# punta.net
KiCad netlist of a schematic drawn in EAGLE
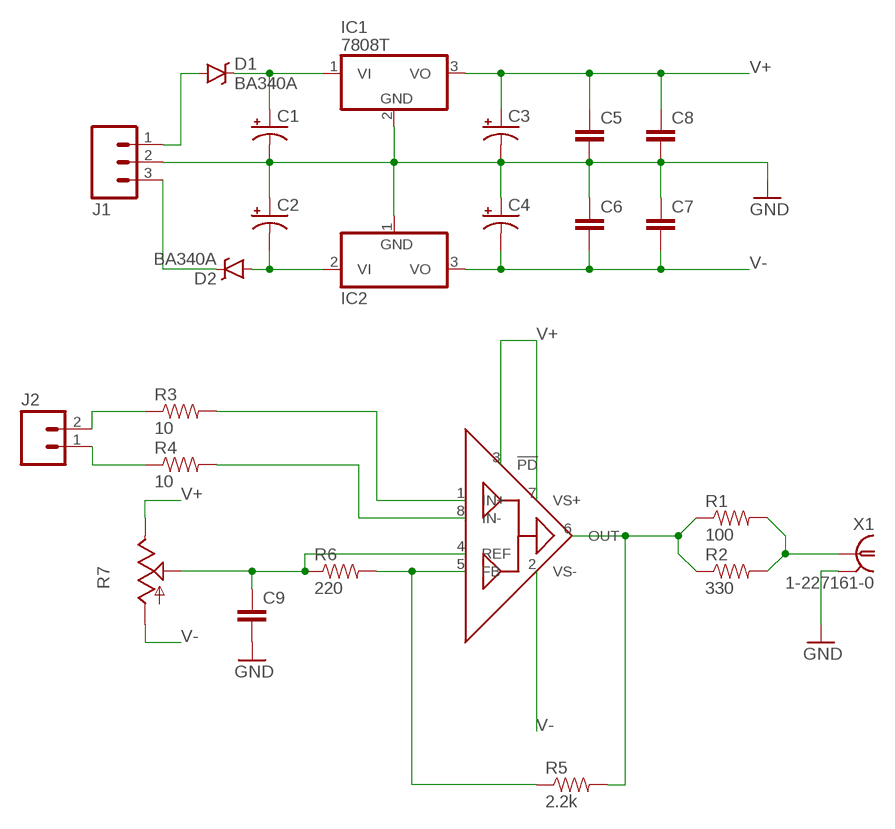
[diagram p0: schematic, sheet 1]

(export (version "E")
  (design (tool "Eeschema 10.0.6"))
  (components
    (comp (ref "C1")
      (value "CAP_POL1206-KIT")
      (footprint "eagle-import:EIA3216-KIT")
      (libsource (lib "eagle-import") (part "CAP_POL1206-KIT"))
    )
    (comp (ref "C2")
      (value "CAP_POL1206-KIT")
      (footprint "eagle-import:EIA3216-KIT")
      (libsource (lib "eagle-import") (part "CAP_POL1206-KIT"))
    )
    (comp (ref "C3")
      (value "CAP_POL1206-KIT")
      (footprint "eagle-import:EIA3216-KIT")
      (libsource (lib "eagle-import") (part "CAP_POL1206-KIT"))
    )
    (comp (ref "C4")
      (value "CAP_POL1206-KIT")
      (footprint "eagle-import:EIA3216-KIT")
      (libsource (lib "eagle-import") (part "CAP_POL1206-KIT"))
    )
    (comp (ref "C5")
      (value "CAP0805")
      (footprint "eagle-import:0805")
      (libsource (lib "eagle-import") (part "CAP0805"))
    )
    (comp (ref "C6")
      (value "CAP0805")
      (footprint "eagle-import:0805")
      (libsource (lib "eagle-import") (part "CAP0805"))
    )
    (comp (ref "C7")
      (value "CAP0805")
      (footprint "eagle-import:0805")
      (libsource (lib "eagle-import") (part "CAP0805"))
    )
    (comp (ref "C8")
      (value "CAP0805")
      (footprint "eagle-import:0805")
      (libsource (lib "eagle-import") (part "CAP0805"))
    )
    (comp (ref "C9")
      (value "CAP0805")
      (footprint "eagle-import:0805")
      (libsource (lib "eagle-import") (part "CAP0805"))
    )
    (comp (ref "D1")
      (value "BA340A")
      (footprint "eagle-import:SMA-DIODE")
      (libsource (lib "eagle-import") (part "B340A"))
    )
    (comp (ref "D2")
      (value "BA340A")
      (footprint "eagle-import:SMA-DIODE")
      (libsource (lib "eagle-import") (part "B340A"))
    )
    (comp (ref "IC1")
      (value "7808T")
      (footprint "eagle-import:TO220H")
      (libsource (lib "eagle-import") (part "78T08"))
    )
    (comp (ref "IC2")
      (value "7908T")
      (footprint "eagle-import:TO220H")
      (libsource (lib "eagle-import") (part "79T08"))
    )
    (comp (ref "J1")
      (value "M03-SCREW-5MM")
      (footprint "eagle-import:SCREWTERMINAL-5MM-3")
      (libsource (lib "eagle-import") (part "M03-SCREW-5MM"))
    )
    (comp (ref "J2")
      (value "M02PTH")
      (footprint "eagle-import:1X02")
      (libsource (lib "eagle-import") (part "M02PTH"))
    )
    (comp (ref "R1")
      (value "100")
      (footprint "eagle-import:0805")
      (libsource (lib "eagle-import") (part "RESISTOR0805-RES"))
    )
    (comp (ref "R2")
      (value "330")
      (footprint "eagle-import:0805")
      (libsource (lib "eagle-import") (part "RESISTOR0805-RES"))
    )
    (comp (ref "R3")
      (value "10")
      (footprint "eagle-import:0805")
      (libsource (lib "eagle-import") (part "RESISTOR0805-RES"))
    )
    (comp (ref "R4")
      (value "10")
      (footprint "eagle-import:0805")
      (libsource (lib "eagle-import") (part "RESISTOR0805-RES"))
    )
    (comp (ref "R5")
      (value "2.2k")
      (footprint "eagle-import:0805")
      (libsource (lib "eagle-import") (part "RESISTOR0805-RES"))
    )
    (comp (ref "R6")
      (value "220")
      (footprint "eagle-import:0805")
      (libsource (lib "eagle-import") (part "RESISTOR0805-RES"))
    )
    (comp (ref "R7")
      (value "TRIM_US-B64Y")
      (footprint "eagle-import:B64Y")
      (libsource (lib "eagle-import") (part "TRIM_US-B64Y"))
    )
    (comp (ref "U$1")
      (value "AD8129ARZ")
      (footprint "eagle-import:SOIC8")
      (libsource (lib "eagle-import") (part "AD8129ARZ"))
    )
    (comp (ref "X1")
      (value "1-227161-0")
      (footprint "eagle-import:AMP_227161")
      (fields (field (name "MF") "TYCO ELECTRONICS") (field (name "MPN") "1-227161"))
      (libsource (lib "eagle-import") (part "?2271611--0"))
    )
  )
  (nets
    (net (code "1") (name "/V+") (class "Default")
      (node (ref "C3") (pin "A") (pinfunction "+_A") (pintype "passive"))
      (node (ref "C5") (pin "1") (pinfunction "1_1") (pintype "passive"))
      (node (ref "C8") (pin "1") (pinfunction "1_1") (pintype "passive"))
      (node (ref "IC1") (pin "3") (pinfunction "VO_3") (pintype "passive"))
      (node (ref "R7") (pin "E") (pinfunction "E_E") (pintype "passive"))
      (node (ref "U$1") (pin "3") (pinfunction "~{PD}_3") (pintype "bidirectional"))
      (node (ref "U$1") (pin "7") (pinfunction "VS+_7") (pintype "bidirectional"))
    )
    (net (code "2") (name "/V-") (class "Default")
      (node (ref "C4") (pin "C") (pinfunction "-_C") (pintype "passive"))
      (node (ref "C6") (pin "2") (pinfunction "2_2") (pintype "passive"))
      (node (ref "C7") (pin "2") (pinfunction "2_2") (pintype "passive"))
      (node (ref "IC2") (pin "3") (pinfunction "VO_3") (pintype "passive"))
      (node (ref "R7") (pin "A") (pinfunction "A_A") (pintype "passive"))
      (node (ref "U$1") (pin "2") (pinfunction "VS-_2") (pintype "bidirectional"))
    )
    (net (code "3") (name "GND") (class "Default")
      (node (ref "C1") (pin "C") (pinfunction "-_C") (pintype "passive"))
      (node (ref "C2") (pin "A") (pinfunction "+_A") (pintype "passive"))
      (node (ref "C3") (pin "C") (pinfunction "-_C") (pintype "passive"))
      (node (ref "C4") (pin "A") (pinfunction "+_A") (pintype "passive"))
      (node (ref "C5") (pin "2") (pinfunction "2_2") (pintype "passive"))
      (node (ref "C6") (pin "1") (pinfunction "1_1") (pintype "passive"))
      (node (ref "C7") (pin "1") (pinfunction "1_1") (pintype "passive"))
      (node (ref "C8") (pin "2") (pinfunction "2_2") (pintype "passive"))
      (node (ref "C9") (pin "2") (pinfunction "2_2") (pintype "passive"))
      (node (ref "IC1") (pin "2") (pinfunction "GND_2") (pintype "passive"))
      (node (ref "IC2") (pin "1") (pinfunction "GND_1") (pintype "passive"))
      (node (ref "J1") (pin "2") (pinfunction "2_2") (pintype "passive"))
      (node (ref "X1") (pin "2") (pinfunction "2_2") (pintype "passive"))
    )
    (net (code "4") (name "Net-(C1-+)") (class "Default")
      (node (ref "C1") (pin "A") (pinfunction "+_A") (pintype "passive"))
      (node (ref "D1") (pin "C") (pinfunction "C_C") (pintype "passive"))
      (node (ref "IC1") (pin "1") (pinfunction "VI_1") (pintype "input"))
    )
    (net (code "5") (name "Net-(C2--)") (class "Default")
      (node (ref "C2") (pin "C") (pinfunction "-_C") (pintype "passive"))
      (node (ref "D2") (pin "A") (pinfunction "A_A") (pintype "passive"))
      (node (ref "IC2") (pin "2") (pinfunction "VI_2") (pintype "input"))
    )
    (net (code "6") (name "Net-(D1-PadA)") (class "Default")
      (node (ref "D1") (pin "A") (pinfunction "A_A") (pintype "passive"))
      (node (ref "J1") (pin "1") (pinfunction "1_1") (pintype "passive"))
    )
    (net (code "7") (name "Net-(D2-PadC)") (class "Default")
      (node (ref "D2") (pin "C") (pinfunction "C_C") (pintype "passive"))
      (node (ref "J1") (pin "3") (pinfunction "3_3") (pintype "passive"))
    )
    (net (code "8") (name "Net-(J2-Pad1)") (class "Default")
      (node (ref "J2") (pin "1") (pinfunction "1_1") (pintype "passive"))
      (node (ref "R4") (pin "1") (pinfunction "1_1") (pintype "passive"))
    )
    (net (code "9") (name "Net-(J2-Pad2)") (class "Default")
      (node (ref "J2") (pin "2") (pinfunction "2_2") (pintype "passive"))
      (node (ref "R3") (pin "1") (pinfunction "1_1") (pintype "passive"))
    )
    (net (code "10") (name "Net-(R1-Pad2)") (class "Default")
      (node (ref "R1") (pin "2") (pinfunction "2_2") (pintype "passive"))
      (node (ref "R2") (pin "2") (pinfunction "2_2") (pintype "passive"))
      (node (ref "X1") (pin "1") (pinfunction "1_1") (pintype "passive"))
    )
    (net (code "11") (name "Net-(U$1-FB)") (class "Default")
      (node (ref "R5") (pin "1") (pinfunction "1_1") (pintype "passive"))
      (node (ref "R6") (pin "2") (pinfunction "2_2") (pintype "passive"))
      (node (ref "U$1") (pin "5") (pinfunction "FB_5") (pintype "bidirectional"))
    )
    (net (code "12") (name "Net-(U$1-IN+)") (class "Default")
      (node (ref "R3") (pin "2") (pinfunction "2_2") (pintype "passive"))
      (node (ref "U$1") (pin "1") (pinfunction "IN+_1") (pintype "bidirectional"))
    )
    (net (code "13") (name "Net-(U$1-IN-)") (class "Default")
      (node (ref "R4") (pin "2") (pinfunction "2_2") (pintype "passive"))
      (node (ref "U$1") (pin "8") (pinfunction "IN-_8") (pintype "bidirectional"))
    )
    (net (code "14") (name "Net-(U$1-OUT)") (class "Default")
      (node (ref "R1") (pin "1") (pinfunction "1_1") (pintype "passive"))
      (node (ref "R2") (pin "1") (pinfunction "1_1") (pintype "passive"))
      (node (ref "R5") (pin "2") (pinfunction "2_2") (pintype "passive"))
      (node (ref "U$1") (pin "6") (pinfunction "OUT_6") (pintype "bidirectional"))
    )
    (net (code "15") (name "Net-(U$1-REF)") (class "Default")
      (node (ref "C9") (pin "1") (pinfunction "1_1") (pintype "passive"))
      (node (ref "R6") (pin "1") (pinfunction "1_1") (pintype "passive"))
      (node (ref "R7") (pin "S") (pinfunction "S_S") (pintype "passive"))
      (node (ref "U$1") (pin "4") (pinfunction "REF_4") (pintype "bidirectional"))
    )
  )
)
